# DDR3.net
KiCad netlist of a schematic drawn in Altium Designer
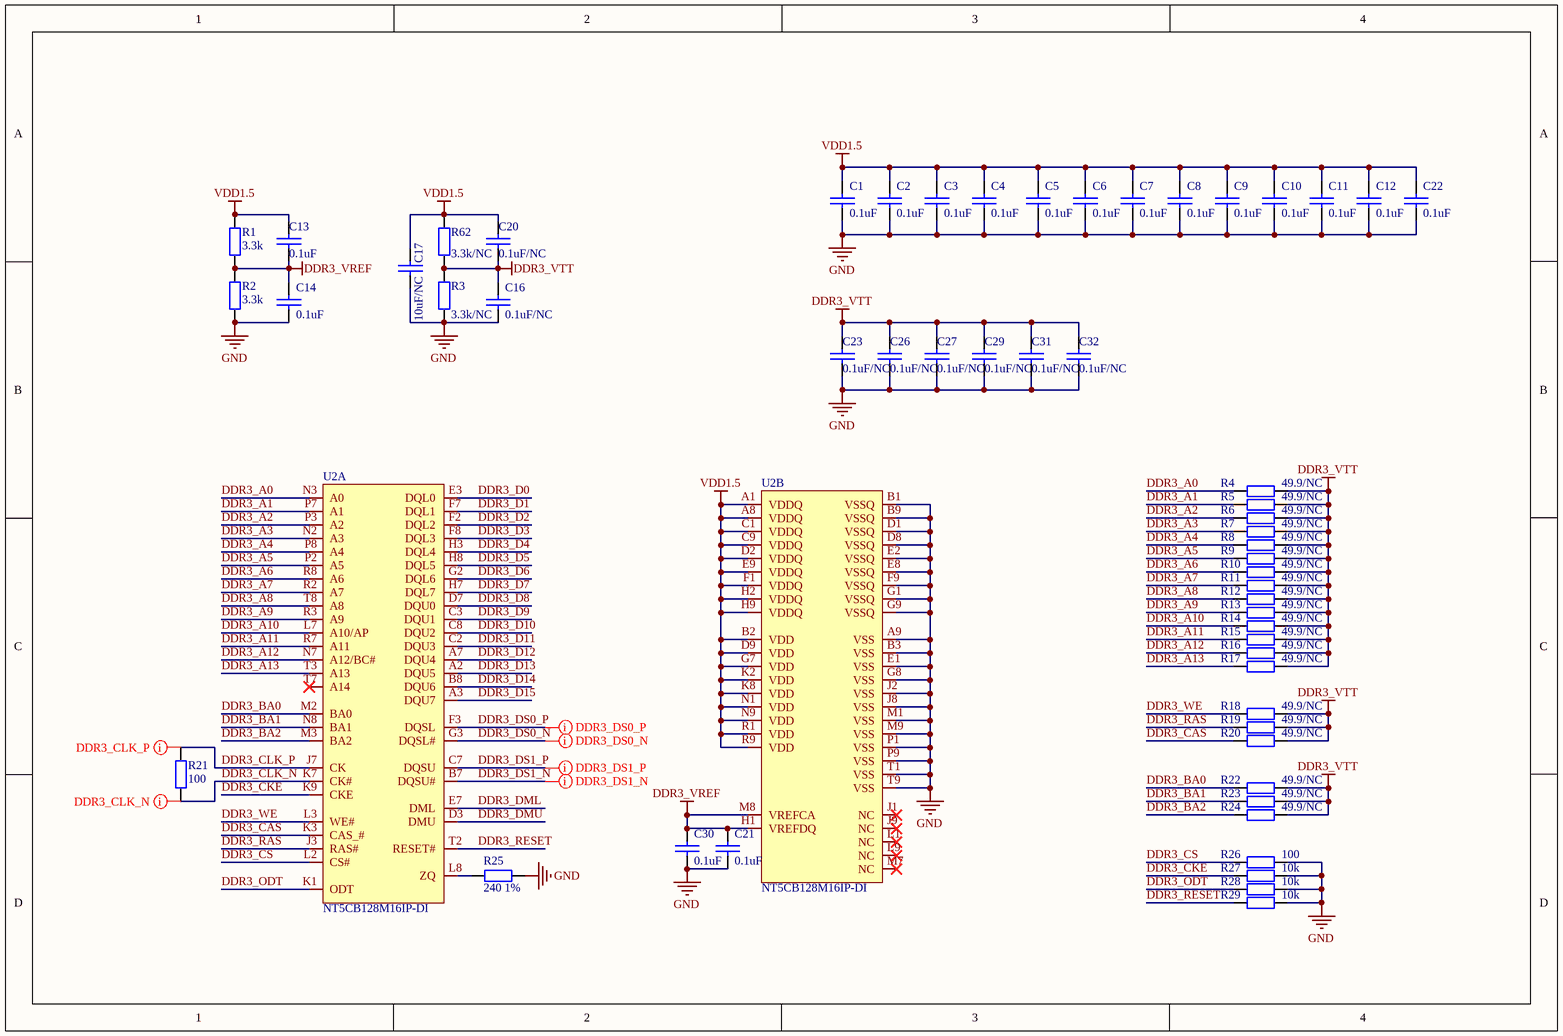
[diagram p0: DDR3.SchDoc]

(export (version "E")
  (design (tool "Eeschema 10.0.6"))
  (components
    (comp (ref "C1") (value "0.1uF") (footprint "0402_c_m") (libsource (lib "My library") (part "CAP")))
    (comp (ref "C2") (value "0.1uF") (footprint "0402_c_m") (libsource (lib "My library") (part "CAP")))
    (comp (ref "C3") (value "0.1uF") (footprint "0402_c_m") (libsource (lib "My library") (part "CAP")))
    (comp (ref "C4") (value "0.1uF") (footprint "0402_c_m") (libsource (lib "My library") (part "CAP")))
    (comp (ref "C5") (value "0.1uF") (footprint "0402_c_m") (libsource (lib "My library") (part "CAP")))
    (comp (ref "C6") (value "0.1uF") (footprint "0402_c_m") (libsource (lib "My library") (part "CAP")))
    (comp (ref "C7") (value "0.1uF") (footprint "0402_c_m") (libsource (lib "My library") (part "CAP")))
    (comp (ref "C8") (value "0.1uF") (footprint "0402_c_m") (libsource (lib "My library") (part "CAP")))
    (comp (ref "C9") (value "0.1uF") (footprint "0402_c_m") (libsource (lib "My library") (part "CAP")))
    (comp (ref "C10") (value "0.1uF") (footprint "0402_c_m") (libsource (lib "My library") (part "CAP")))
    (comp (ref "C11") (value "0.1uF") (footprint "0402_c_m") (libsource (lib "My library") (part "CAP")))
    (comp (ref "C12") (value "0.1uF") (footprint "0402_c_m") (libsource (lib "My library") (part "CAP")))
    (comp (ref "C13") (value "0.1uF") (footprint "0402_c_m") (libsource (lib "My library") (part "CAP")))
    (comp (ref "C14") (value "0.1uF") (footprint "0402_c_m") (libsource (lib "My library") (part "CAP")))
    (comp (ref "C16") (value "0.1uF/NC") (footprint "0402_c_m") (libsource (lib "My library") (part "CAP")))
    (comp (ref "C17") (value "10uF/NC") (footprint "0603_c_m") (libsource (lib "My library") (part "CAP")))
    (comp (ref "C20") (value "0.1uF/NC") (footprint "0402_c_m") (libsource (lib "My library") (part "CAP")))
    (comp (ref "C21") (value "0.1uF") (footprint "0402_c_m") (libsource (lib "My library") (part "CAP")))
    (comp (ref "C22") (value "0.1uF") (footprint "0402_c_m") (libsource (lib "My library") (part "CAP")))
    (comp (ref "C23") (value "0.1uF/NC") (footprint "0402_c_m") (libsource (lib "My library") (part "CAP")))
    (comp (ref "C26") (value "0.1uF/NC") (footprint "0402_c_m") (libsource (lib "My library") (part "CAP")))
    (comp (ref "C27") (value "0.1uF/NC") (footprint "0402_c_m") (libsource (lib "My library") (part "CAP")))
    (comp (ref "C29") (value "0.1uF/NC") (footprint "0402_c_m") (libsource (lib "My library") (part "CAP")))
    (comp (ref "C30") (value "0.1uF") (footprint "0402_c_m") (libsource (lib "My library") (part "CAP")))
    (comp (ref "C31") (value "0.1uF/NC") (footprint "0402_c_m") (libsource (lib "My library") (part "CAP")))
    (comp (ref "C32") (value "0.1uF/NC") (footprint "0402_c_m") (libsource (lib "My library") (part "CAP")))
    (comp (ref "R1") (value "3.3k") (footprint "0402_r_m") (libsource (lib "My Library") (part "RES2")))
    (comp (ref "R2") (value "3.3k") (footprint "0402_r_m") (libsource (lib "My Library") (part "RES2")))
    (comp (ref "R3") (value "3.3k/NC") (footprint "0402_r_m") (libsource (lib "My Library") (part "RES2")))
    (comp (ref "R4") (value "49.9/NC") (footprint "0402_r_m") (libsource (lib "My Library") (part "RES2")))
    (comp (ref "R5") (value "49.9/NC") (footprint "0402_r_m") (libsource (lib "My Library") (part "RES2")))
    (comp (ref "R6") (value "49.9/NC") (footprint "0402_r_m") (libsource (lib "My Library") (part "RES2")))
    (comp (ref "R7") (value "49.9/NC") (footprint "0402_r_m") (libsource (lib "My Library") (part "RES2")))
    (comp (ref "R8") (value "49.9/NC") (footprint "0402_r_m") (libsource (lib "My Library") (part "RES2")))
    (comp (ref "R9") (value "49.9/NC") (footprint "0402_r_m") (libsource (lib "My Library") (part "RES2")))
    (comp (ref "R10") (value "49.9/NC") (footprint "0402_r_m") (libsource (lib "My Library") (part "RES2")))
    (comp (ref "R11") (value "49.9/NC") (footprint "0402_r_m") (libsource (lib "My Library") (part "RES2")))
    (comp (ref "R12") (value "49.9/NC") (footprint "0402_r_m") (libsource (lib "My Library") (part "RES2")))
    (comp (ref "R13") (value "49.9/NC") (footprint "0402_r_m") (libsource (lib "My Library") (part "RES2")))
    (comp (ref "R14") (value "49.9/NC") (footprint "0402_r_m") (libsource (lib "My Library") (part "RES2")))
    (comp (ref "R15") (value "49.9/NC") (footprint "0402_r_m") (libsource (lib "My Library") (part "RES2")))
    (comp (ref "R16") (value "49.9/NC") (footprint "0402_r_m") (libsource (lib "My Library") (part "RES2")))
    (comp (ref "R17") (value "49.9/NC") (footprint "0402_r_m") (libsource (lib "My Library") (part "RES2")))
    (comp (ref "R18") (value "49.9/NC") (footprint "0402_r_m") (libsource (lib "My Library") (part "RES2")))
    (comp (ref "R19") (value "49.9/NC") (footprint "0402_r_m") (libsource (lib "My Library") (part "RES2")))
    (comp (ref "R20") (value "49.9/NC") (footprint "0402_r_m") (libsource (lib "My Library") (part "RES2")))
    (comp (ref "R21") (value "100") (footprint "0402_r_m") (libsource (lib "My Library") (part "RES2")))
    (comp (ref "R22") (value "49.9/NC") (footprint "0402_r_m") (libsource (lib "My Library") (part "RES2")))
    (comp (ref "R23") (value "49.9/NC") (footprint "0402_r_m") (libsource (lib "My Library") (part "RES2")))
    (comp (ref "R24") (value "49.9/NC") (footprint "0402_r_m") (libsource (lib "My Library") (part "RES2")))
    (comp (ref "R25") (value "240 1%") (footprint "0402_R_M") (libsource (lib "Common") (part "RES2")))
    (comp (ref "R26") (value "100") (footprint "0402_r_m") (libsource (lib "My Library") (part "RES2")))
    (comp (ref "R27") (value "10k") (footprint "0402_r_m") (libsource (lib "My Library") (part "RES2")))
    (comp (ref "R28") (value "10k") (footprint "0402_r_m") (libsource (lib "My Library") (part "RES2")))
    (comp (ref "R29") (value "10k") (footprint "0402_r_m") (libsource (lib "My Library") (part "RES2")))
    (comp (ref "R62") (value "3.3k/NC") (footprint "0402_r_m") (libsource (lib "My Library") (part "RES2")))
    (comp (ref "U2")
      (value "NT5CB128M16IP-DI")
      (footprint "TFBGA96")
      (libsource (lib "XC7A200T") (part "NT5CB128M16IP-DI"))
    )
  )
  (nets
    (net (code "1") (name "/DDR3_A0") (class "Default")
      (node (ref "R4") (pin "1") (pintype "passive"))
      (node (ref "U2") (pin "N3") (pinfunction "A0_N3") (pintype "passive"))
    )
    (net (code "2") (name "/DDR3_A1") (class "Default")
      (node (ref "R5") (pin "1") (pintype "passive"))
      (node (ref "U2") (pin "P7") (pinfunction "A1_P7") (pintype "passive"))
    )
    (net (code "3") (name "/DDR3_A2") (class "Default")
      (node (ref "R6") (pin "1") (pintype "passive"))
      (node (ref "U2") (pin "P3") (pinfunction "A2_P3") (pintype "passive"))
    )
    (net (code "4") (name "/DDR3_A3") (class "Default")
      (node (ref "R7") (pin "1") (pintype "passive"))
      (node (ref "U2") (pin "N2") (pinfunction "A3_N2") (pintype "passive"))
    )
    (net (code "5") (name "/DDR3_A4") (class "Default")
      (node (ref "R8") (pin "1") (pintype "passive"))
      (node (ref "U2") (pin "P8") (pinfunction "A4_P8") (pintype "passive"))
    )
    (net (code "6") (name "/DDR3_A5") (class "Default")
      (node (ref "R9") (pin "1") (pintype "passive"))
      (node (ref "U2") (pin "P2") (pinfunction "A5_P2") (pintype "passive"))
    )
    (net (code "7") (name "/DDR3_A6") (class "Default")
      (node (ref "R10") (pin "1") (pintype "passive"))
      (node (ref "U2") (pin "R8") (pinfunction "A6_R8") (pintype "passive"))
    )
    (net (code "8") (name "/DDR3_A7") (class "Default")
      (node (ref "R11") (pin "1") (pintype "passive"))
      (node (ref "U2") (pin "R2") (pinfunction "A7_R2") (pintype "passive"))
    )
    (net (code "9") (name "/DDR3_A8") (class "Default")
      (node (ref "R12") (pin "1") (pintype "passive"))
      (node (ref "U2") (pin "T8") (pinfunction "A8_T8") (pintype "passive"))
    )
    (net (code "10") (name "/DDR3_A9") (class "Default")
      (node (ref "R13") (pin "1") (pintype "passive"))
      (node (ref "U2") (pin "R3") (pinfunction "A9_R3") (pintype "passive"))
    )
    (net (code "11") (name "/DDR3_A10") (class "Default")
      (node (ref "R14") (pin "1") (pintype "passive"))
      (node (ref "U2") (pin "L7") (pinfunction "A10/AP_L7") (pintype "passive"))
    )
    (net (code "12") (name "/DDR3_A11") (class "Default")
      (node (ref "R15") (pin "1") (pintype "passive"))
      (node (ref "U2") (pin "R7") (pinfunction "A11_R7") (pintype "passive"))
    )
    (net (code "13") (name "/DDR3_A12") (class "Default")
      (node (ref "R16") (pin "1") (pintype "passive"))
      (node (ref "U2") (pin "N7") (pinfunction "A12/BC#_N7") (pintype "passive"))
    )
    (net (code "14") (name "/DDR3_A13") (class "Default")
      (node (ref "R17") (pin "1") (pintype "passive"))
      (node (ref "U2") (pin "T3") (pinfunction "A13_T3") (pintype "passive"))
    )
    (net (code "15") (name "/DDR3_BA0") (class "Default")
      (node (ref "R22") (pin "1") (pintype "passive"))
      (node (ref "U2") (pin "M2") (pinfunction "BA0_M2") (pintype "passive"))
    )
    (net (code "16") (name "/DDR3_BA1") (class "Default")
      (node (ref "R23") (pin "1") (pintype "passive"))
      (node (ref "U2") (pin "N8") (pinfunction "BA1_N8") (pintype "passive"))
    )
    (net (code "17") (name "/DDR3_BA2") (class "Default")
      (node (ref "R24") (pin "1") (pintype "passive"))
      (node (ref "U2") (pin "M3") (pinfunction "BA2_M3") (pintype "passive"))
    )
    (net (code "18") (name "/DDR3_CAS") (class "Default")
      (node (ref "R20") (pin "1") (pintype "passive"))
      (node (ref "U2") (pin "K3") (pinfunction "CAS_#_K3") (pintype "passive"))
    )
    (net (code "19") (name "/DDR3_CKE") (class "Default")
      (node (ref "R27") (pin "1") (pintype "passive"))
      (node (ref "U2") (pin "K9") (pinfunction "CKE_K9") (pintype "passive"))
    )
    (net (code "20") (name "/DDR3_CLK_N") (class "Default")
      (node (ref "R21") (pin "1") (pintype "passive"))
      (node (ref "U2") (pin "K7") (pinfunction "CK#_K7") (pintype "passive"))
    )
    (net (code "21") (name "/DDR3_CLK_P") (class "Default")
      (node (ref "R21") (pin "2") (pintype "passive"))
      (node (ref "U2") (pin "J7") (pinfunction "CK_J7") (pintype "passive"))
    )
    (net (code "22") (name "/DDR3_CS") (class "Default")
      (node (ref "R26") (pin "1") (pintype "passive"))
      (node (ref "U2") (pin "L2") (pinfunction "CS#_L2") (pintype "passive"))
    )
    (net (code "23") (name "/DDR3_D0") (class "Default")
      (node (ref "U2") (pin "E3") (pinfunction "DQL0_E3") (pintype "passive"))
    )
    (net (code "24") (name "/DDR3_D1") (class "Default")
      (node (ref "U2") (pin "F7") (pinfunction "DQL1_F7") (pintype "passive"))
    )
    (net (code "25") (name "/DDR3_D2") (class "Default")
      (node (ref "U2") (pin "F2") (pinfunction "DQL2_F2") (pintype "passive"))
    )
    (net (code "26") (name "/DDR3_D3") (class "Default")
      (node (ref "U2") (pin "F8") (pinfunction "DQL3_F8") (pintype "passive"))
    )
    (net (code "27") (name "/DDR3_D4") (class "Default")
      (node (ref "U2") (pin "H3") (pinfunction "DQL4_H3") (pintype "passive"))
    )
    (net (code "28") (name "/DDR3_D5") (class "Default")
      (node (ref "U2") (pin "H8") (pinfunction "DQL5_H8") (pintype "passive"))
    )
    (net (code "29") (name "/DDR3_D6") (class "Default")
      (node (ref "U2") (pin "G2") (pinfunction "DQL6_G2") (pintype "passive"))
    )
    (net (code "30") (name "/DDR3_D7") (class "Default")
      (node (ref "U2") (pin "H7") (pinfunction "DQL7_H7") (pintype "passive"))
    )
    (net (code "31") (name "/DDR3_D8") (class "Default")
      (node (ref "U2") (pin "D7") (pinfunction "DQU0_D7") (pintype "passive"))
    )
    (net (code "32") (name "/DDR3_D9") (class "Default")
      (node (ref "U2") (pin "C3") (pinfunction "DQU1_C3") (pintype "passive"))
    )
    (net (code "33") (name "/DDR3_D10") (class "Default")
      (node (ref "U2") (pin "C8") (pinfunction "DQU2_C8") (pintype "passive"))
    )
    (net (code "34") (name "/DDR3_D11") (class "Default")
      (node (ref "U2") (pin "C2") (pinfunction "DQU3_C2") (pintype "passive"))
    )
    (net (code "35") (name "/DDR3_D12") (class "Default")
      (node (ref "U2") (pin "A7") (pinfunction "DQU4_A7") (pintype "passive"))
    )
    (net (code "36") (name "/DDR3_D13") (class "Default")
      (node (ref "U2") (pin "A2") (pinfunction "DQU5_A2") (pintype "passive"))
    )
    (net (code "37") (name "/DDR3_D14") (class "Default")
      (node (ref "U2") (pin "B8") (pinfunction "DQU6_B8") (pintype "passive"))
    )
    (net (code "38") (name "/DDR3_D15") (class "Default")
      (node (ref "U2") (pin "A3") (pinfunction "DQU7_A3") (pintype "passive"))
    )
    (net (code "39") (name "/DDR3_DML") (class "Default")
      (node (ref "U2") (pin "E7") (pinfunction "DML_E7") (pintype "passive"))
    )
    (net (code "40") (name "/DDR3_DMU") (class "Default")
      (node (ref "U2") (pin "D3") (pinfunction "DMU_D3") (pintype "passive"))
    )
    (net (code "41") (name "/DDR3_DS0_N") (class "Default")
      (node (ref "U2") (pin "G3") (pinfunction "DQSL#_G3") (pintype "passive"))
    )
    (net (code "42") (name "/DDR3_DS0_P") (class "Default")
      (node (ref "U2") (pin "F3") (pinfunction "DQSL_F3") (pintype "passive"))
    )
    (net (code "43") (name "/DDR3_DS1_N") (class "Default")
      (node (ref "U2") (pin "B7") (pinfunction "DQSU#_B7") (pintype "passive"))
    )
    (net (code "44") (name "/DDR3_DS1_P") (class "Default")
      (node (ref "U2") (pin "C7") (pinfunction "DQSU_C7") (pintype "passive"))
    )
    (net (code "45") (name "/DDR3_ODT") (class "Default")
      (node (ref "R28") (pin "1") (pintype "passive"))
      (node (ref "U2") (pin "K1") (pinfunction "ODT_K1") (pintype "passive"))
    )
    (net (code "46") (name "/DDR3_RAS") (class "Default")
      (node (ref "R19") (pin "1") (pintype "passive"))
      (node (ref "U2") (pin "J3") (pinfunction "RAS#_J3") (pintype "passive"))
    )
    (net (code "47") (name "/DDR3_RESET") (class "Default")
      (node (ref "R29") (pin "1") (pintype "passive"))
      (node (ref "U2") (pin "T2") (pinfunction "RESET#_T2") (pintype "passive"))
    )
    (net (code "48") (name "/DDR3_WE") (class "Default")
      (node (ref "R18") (pin "1") (pintype "passive"))
      (node (ref "U2") (pin "L3") (pinfunction "WE#_L3") (pintype "passive"))
    )
    (net (code "49") (name "DDR3_VREF") (class "Default")
      (node (ref "C13") (pin "2") (pinfunction "2_2") (pintype "passive"))
      (node (ref "C14") (pin "1") (pinfunction "1_1") (pintype "passive"))
      (node (ref "C21") (pin "1") (pinfunction "1_1") (pintype "passive"))
      (node (ref "C30") (pin "1") (pinfunction "1_1") (pintype "passive"))
      (node (ref "R1") (pin "1") (pintype "passive"))
      (node (ref "R2") (pin "2") (pintype "passive"))
      (node (ref "U2") (pin "H1") (pinfunction "VREFDQ_H1") (pintype "passive"))
      (node (ref "U2") (pin "M8") (pinfunction "VREFCA_M8") (pintype "passive"))
    )
    (net (code "50") (name "DDR3_VTT") (class "Default")
      (node (ref "C16") (pin "1") (pinfunction "1_1") (pintype "passive"))
      (node (ref "C20") (pin "2") (pinfunction "2_2") (pintype "passive"))
      (node (ref "C23") (pin "1") (pinfunction "1_1") (pintype "passive"))
      (node (ref "C26") (pin "1") (pinfunction "1_1") (pintype "passive"))
      (node (ref "C27") (pin "1") (pinfunction "1_1") (pintype "passive"))
      (node (ref "C29") (pin "1") (pinfunction "1_1") (pintype "passive"))
      (node (ref "C31") (pin "1") (pinfunction "1_1") (pintype "passive"))
      (node (ref "C32") (pin "1") (pinfunction "1_1") (pintype "passive"))
      (node (ref "R10") (pin "2") (pintype "passive"))
      (node (ref "R11") (pin "2") (pintype "passive"))
      (node (ref "R12") (pin "2") (pintype "passive"))
      (node (ref "R13") (pin "2") (pintype "passive"))
      (node (ref "R14") (pin "2") (pintype "passive"))
      (node (ref "R15") (pin "2") (pintype "passive"))
      (node (ref "R16") (pin "2") (pintype "passive"))
      (node (ref "R17") (pin "2") (pintype "passive"))
      (node (ref "R18") (pin "2") (pintype "passive"))
      (node (ref "R19") (pin "2") (pintype "passive"))
      (node (ref "R20") (pin "2") (pintype "passive"))
      (node (ref "R22") (pin "2") (pintype "passive"))
      (node (ref "R23") (pin "2") (pintype "passive"))
      (node (ref "R24") (pin "2") (pintype "passive"))
      (node (ref "R3") (pin "2") (pintype "passive"))
      (node (ref "R4") (pin "2") (pintype "passive"))
      (node (ref "R5") (pin "2") (pintype "passive"))
      (node (ref "R6") (pin "2") (pintype "passive"))
      (node (ref "R62") (pin "1") (pintype "passive"))
      (node (ref "R7") (pin "2") (pintype "passive"))
      (node (ref "R8") (pin "2") (pintype "passive"))
      (node (ref "R9") (pin "2") (pintype "passive"))
    )
    (net (code "51") (name "GND") (class "Default")
      (node (ref "C1") (pin "2") (pinfunction "2_2") (pintype "passive"))
      (node (ref "C10") (pin "2") (pinfunction "2_2") (pintype "passive"))
      (node (ref "C11") (pin "2") (pinfunction "2_2") (pintype "passive"))
      (node (ref "C12") (pin "2") (pinfunction "2_2") (pintype "passive"))
      (node (ref "C14") (pin "2") (pinfunction "2_2") (pintype "passive"))
      (node (ref "C16") (pin "2") (pinfunction "2_2") (pintype "passive"))
      (node (ref "C17") (pin "2") (pinfunction "2_2") (pintype "passive"))
      (node (ref "C2") (pin "2") (pinfunction "2_2") (pintype "passive"))
      (node (ref "C21") (pin "2") (pinfunction "2_2") (pintype "passive"))
      (node (ref "C22") (pin "2") (pinfunction "2_2") (pintype "passive"))
      (node (ref "C23") (pin "2") (pinfunction "2_2") (pintype "passive"))
      (node (ref "C26") (pin "2") (pinfunction "2_2") (pintype "passive"))
      (node (ref "C27") (pin "2") (pinfunction "2_2") (pintype "passive"))
      (node (ref "C29") (pin "2") (pinfunction "2_2") (pintype "passive"))
      (node (ref "C3") (pin "2") (pinfunction "2_2") (pintype "passive"))
      (node (ref "C30") (pin "2") (pinfunction "2_2") (pintype "passive"))
      (node (ref "C31") (pin "2") (pinfunction "2_2") (pintype "passive"))
      (node (ref "C32") (pin "2") (pinfunction "2_2") (pintype "passive"))
      (node (ref "C4") (pin "2") (pinfunction "2_2") (pintype "passive"))
      (node (ref "C5") (pin "2") (pinfunction "2_2") (pintype "passive"))
      (node (ref "C6") (pin "2") (pinfunction "2_2") (pintype "passive"))
      (node (ref "C7") (pin "2") (pinfunction "2_2") (pintype "passive"))
      (node (ref "C8") (pin "2") (pinfunction "2_2") (pintype "passive"))
      (node (ref "C9") (pin "2") (pinfunction "2_2") (pintype "passive"))
      (node (ref "R2") (pin "1") (pintype "passive"))
      (node (ref "R25") (pin "1") (pintype "passive"))
      (node (ref "R26") (pin "2") (pintype "passive"))
      (node (ref "R27") (pin "2") (pintype "passive"))
      (node (ref "R28") (pin "2") (pintype "passive"))
      (node (ref "R29") (pin "2") (pintype "passive"))
      (node (ref "R3") (pin "1") (pintype "passive"))
      (node (ref "U2") (pin "A9") (pinfunction "VSS_A9") (pintype "passive"))
      (node (ref "U2") (pin "B1") (pinfunction "VSSQ_B1") (pintype "passive"))
      (node (ref "U2") (pin "B3") (pinfunction "VSS_B3") (pintype "passive"))
      (node (ref "U2") (pin "B9") (pinfunction "VSSQ_B9") (pintype "passive"))
      (node (ref "U2") (pin "D1") (pinfunction "VSSQ_D1") (pintype "passive"))
      (node (ref "U2") (pin "D8") (pinfunction "VSSQ_D8") (pintype "passive"))
      (node (ref "U2") (pin "E1") (pinfunction "VSS_E1") (pintype "passive"))
      (node (ref "U2") (pin "E2") (pinfunction "VSSQ_E2") (pintype "passive"))
      (node (ref "U2") (pin "E8") (pinfunction "VSSQ_E8") (pintype "passive"))
      (node (ref "U2") (pin "F9") (pinfunction "VSSQ_F9") (pintype "passive"))
      (node (ref "U2") (pin "G1") (pinfunction "VSSQ_G1") (pintype "passive"))
      (node (ref "U2") (pin "G8") (pinfunction "VSS_G8") (pintype "passive"))
      (node (ref "U2") (pin "G9") (pinfunction "VSSQ_G9") (pintype "passive"))
      (node (ref "U2") (pin "J2") (pinfunction "VSS_J2") (pintype "passive"))
      (node (ref "U2") (pin "J8") (pinfunction "VSS_J8") (pintype "passive"))
      (node (ref "U2") (pin "M1") (pinfunction "VSS_M1") (pintype "passive"))
      (node (ref "U2") (pin "M9") (pinfunction "VSS_M9") (pintype "passive"))
      (node (ref "U2") (pin "P1") (pinfunction "VSS_P1") (pintype "passive"))
      (node (ref "U2") (pin "P9") (pinfunction "VSS_P9") (pintype "passive"))
      (node (ref "U2") (pin "T1") (pinfunction "VSS_T1") (pintype "passive"))
      (node (ref "U2") (pin "T9") (pinfunction "VSS_T9") (pintype "passive"))
    )
    (net (code "52") (name "Net-(U2A-ZQ)") (class "Default")
      (node (ref "R25") (pin "2") (pintype "passive"))
      (node (ref "U2") (pin "L8") (pinfunction "ZQ_L8") (pintype "passive"))
    )
    (net (code "53") (name "VDD1.5") (class "Default")
      (node (ref "C1") (pin "1") (pinfunction "1_1") (pintype "passive"))
      (node (ref "C10") (pin "1") (pinfunction "1_1") (pintype "passive"))
      (node (ref "C11") (pin "1") (pinfunction "1_1") (pintype "passive"))
      (node (ref "C12") (pin "1") (pinfunction "1_1") (pintype "passive"))
      (node (ref "C13") (pin "1") (pinfunction "1_1") (pintype "passive"))
      (node (ref "C17") (pin "1") (pinfunction "1_1") (pintype "passive"))
      (node (ref "C2") (pin "1") (pinfunction "1_1") (pintype "passive"))
      (node (ref "C20") (pin "1") (pinfunction "1_1") (pintype "passive"))
      (node (ref "C22") (pin "1") (pinfunction "1_1") (pintype "passive"))
      (node (ref "C3") (pin "1") (pinfunction "1_1") (pintype "passive"))
      (node (ref "C4") (pin "1") (pinfunction "1_1") (pintype "passive"))
      (node (ref "C5") (pin "1") (pinfunction "1_1") (pintype "passive"))
      (node (ref "C6") (pin "1") (pinfunction "1_1") (pintype "passive"))
      (node (ref "C7") (pin "1") (pinfunction "1_1") (pintype "passive"))
      (node (ref "C8") (pin "1") (pinfunction "1_1") (pintype "passive"))
      (node (ref "C9") (pin "1") (pinfunction "1_1") (pintype "passive"))
      (node (ref "R1") (pin "2") (pintype "passive"))
      (node (ref "R62") (pin "2") (pintype "passive"))
      (node (ref "U2") (pin "A1") (pinfunction "VDDQ_A1") (pintype "passive"))
      (node (ref "U2") (pin "A8") (pinfunction "VDDQ_A8") (pintype "passive"))
      (node (ref "U2") (pin "B2") (pinfunction "VDD_B2") (pintype "passive"))
      (node (ref "U2") (pin "C1") (pinfunction "VDDQ_C1") (pintype "passive"))
      (node (ref "U2") (pin "C9") (pinfunction "VDDQ_C9") (pintype "passive"))
      (node (ref "U2") (pin "D2") (pinfunction "VDDQ_D2") (pintype "passive"))
      (node (ref "U2") (pin "D9") (pinfunction "VDD_D9") (pintype "passive"))
      (node (ref "U2") (pin "E9") (pinfunction "VDDQ_E9") (pintype "passive"))
      (node (ref "U2") (pin "F1") (pinfunction "VDDQ_F1") (pintype "passive"))
      (node (ref "U2") (pin "G7") (pinfunction "VDD_G7") (pintype "passive"))
      (node (ref "U2") (pin "H2") (pinfunction "VDDQ_H2") (pintype "passive"))
      (node (ref "U2") (pin "H9") (pinfunction "VDDQ_H9") (pintype "passive"))
      (node (ref "U2") (pin "K2") (pinfunction "VDD_K2") (pintype "passive"))
      (node (ref "U2") (pin "K8") (pinfunction "VDD_K8") (pintype "passive"))
      (node (ref "U2") (pin "N1") (pinfunction "VDD_N1") (pintype "passive"))
      (node (ref "U2") (pin "N9") (pinfunction "VDD_N9") (pintype "passive"))
      (node (ref "U2") (pin "R1") (pinfunction "VDD_R1") (pintype "passive"))
      (node (ref "U2") (pin "R9") (pinfunction "VDD_R9") (pintype "passive"))
    )
    (net (code "54") (name "unconnected-(U2A-A14-PadT7)") (class "Default")
      (node (ref "U2") (pin "T7") (pinfunction "A14_T7") (pintype "passive+no_connect"))
    )
    (net (code "55") (name "unconnected-(U2B-NC-PadJ1)") (class "Default")
      (node (ref "U2") (pin "J1") (pinfunction "NC_J1") (pintype "passive+no_connect"))
    )
    (net (code "56") (name "unconnected-(U2B-NC-PadJ9)") (class "Default")
      (node (ref "U2") (pin "J9") (pinfunction "NC_J9") (pintype "passive+no_connect"))
    )
    (net (code "57") (name "unconnected-(U2B-NC-PadL1)") (class "Default")
      (node (ref "U2") (pin "L1") (pinfunction "NC_L1") (pintype "passive+no_connect"))
    )
    (net (code "58") (name "unconnected-(U2B-NC-PadL9)") (class "Default")
      (node (ref "U2") (pin "L9") (pinfunction "NC_L9") (pintype "passive+no_connect"))
    )
    (net (code "59") (name "unconnected-(U2B-NC-PadM7)") (class "Default")
      (node (ref "U2") (pin "M7") (pinfunction "NC_M7") (pintype "passive+no_connect"))
    )
  )
)
